# video.net
KiCad netlist of a schematic drawn in EAGLE
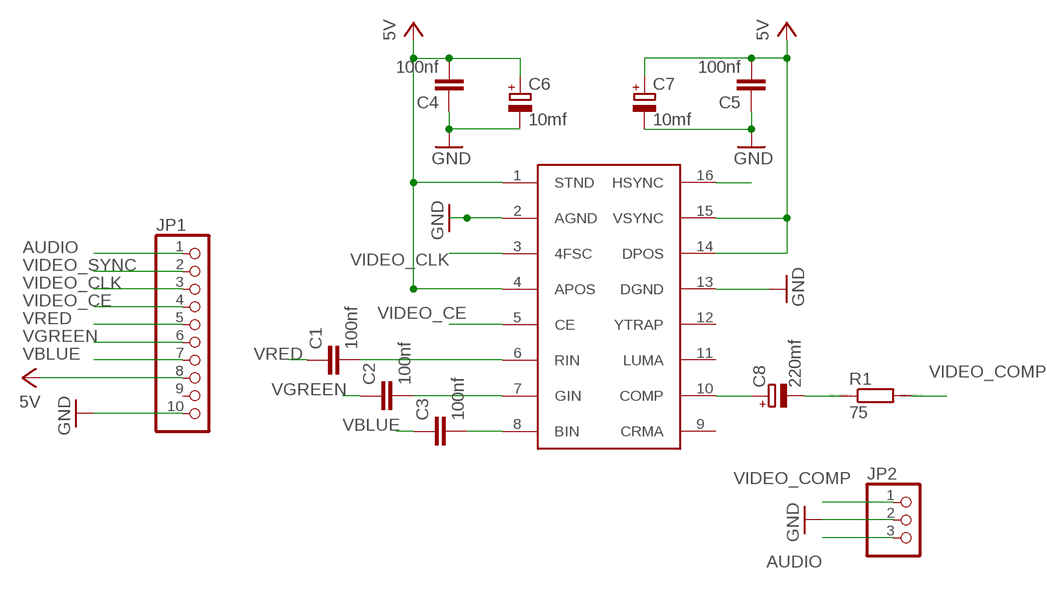
[diagram p0: schematic, sheet 1]

(export (version "E")
  (design (tool "Eeschema 10.0.6"))
  (components
    (comp (ref "C1")
      (value "100nf")
      (footprint "eagle-import:C0805")
      (libsource (lib "eagle-import") (part "C-EUC0805"))
    )
    (comp (ref "C2")
      (value "100nf")
      (footprint "eagle-import:C0805")
      (libsource (lib "eagle-import") (part "C-EUC0805"))
    )
    (comp (ref "C3")
      (value "100nf")
      (footprint "eagle-import:C0805")
      (libsource (lib "eagle-import") (part "C-EUC0805"))
    )
    (comp (ref "C4")
      (value "100nf")
      (footprint "eagle-import:C0805")
      (libsource (lib "eagle-import") (part "C-EUC0805"))
    )
    (comp (ref "C5")
      (value "100nf")
      (footprint "eagle-import:C0805")
      (libsource (lib "eagle-import") (part "C-EUC0805"))
    )
    (comp (ref "C6")
      (value "10mf")
      (footprint "eagle-import:E1,8-4")
      (libsource (lib "eagle-import") (part "CPOL-EUE1.8-4"))
    )
    (comp (ref "C7")
      (value "10mf")
      (footprint "eagle-import:E1,8-4")
      (libsource (lib "eagle-import") (part "CPOL-EUE1.8-4"))
    )
    (comp (ref "C8")
      (value "220mf")
      (footprint "eagle-import:E1,8-4")
      (libsource (lib "eagle-import") (part "CPOL-EUE1.8-4"))
    )
    (comp (ref "JP1")
      (value "PINHD-1X10")
      (footprint "eagle-import:1X10")
      (libsource (lib "eagle-import") (part "PINHD-1X10"))
    )
    (comp (ref "JP2")
      (value "PINHD-1X3")
      (footprint "eagle-import:1X03")
      (libsource (lib "eagle-import") (part "PINHD-1X3"))
    )
    (comp (ref "R1")
      (value "75")
      (footprint "eagle-import:R0805")
      (libsource (lib "eagle-import") (part "R-EU_R0805"))
    )
    (comp (ref "U$1")
      (value "AD725")
      (footprint "eagle-import:SO16W")
      (libsource (lib "eagle-import") (part "AD725"))
    )
  )
  (nets
    (net (code "1") (name "/AUDIO") (class "Default")
      (node (ref "JP1") (pin "1") (pinfunction "1_1") (pintype "passive"))
      (node (ref "JP2") (pin "3") (pinfunction "3_3") (pintype "passive"))
    )
    (net (code "2") (name "/VBLUE") (class "Default")
      (node (ref "C3") (pin "1") (pinfunction "1_1") (pintype "passive"))
      (node (ref "JP1") (pin "7") (pinfunction "7_7") (pintype "passive"))
    )
    (net (code "3") (name "/VGREEN") (class "Default")
      (node (ref "C2") (pin "1") (pinfunction "1_1") (pintype "passive"))
      (node (ref "JP1") (pin "6") (pinfunction "6_6") (pintype "passive"))
    )
    (net (code "4") (name "/VIDEO_CE") (class "Default")
      (node (ref "JP1") (pin "4") (pinfunction "4_4") (pintype "passive"))
      (node (ref "U$1") (pin "5") (pinfunction "CE_5") (pintype "bidirectional"))
    )
    (net (code "5") (name "/VIDEO_CLK") (class "Default")
      (node (ref "JP1") (pin "3") (pinfunction "3_3") (pintype "passive"))
      (node (ref "U$1") (pin "3") (pinfunction "4FSC_3") (pintype "bidirectional"))
    )
    (net (code "6") (name "/VIDEO_COMP") (class "Default")
      (node (ref "JP2") (pin "1") (pinfunction "1_1") (pintype "passive"))
      (node (ref "R1") (pin "2") (pinfunction "2_2") (pintype "passive"))
    )
    (net (code "7") (name "/VIDEO_SYNC") (class "Default")
      (node (ref "JP1") (pin "2") (pinfunction "2_2") (pintype "passive"))
      (node (ref "U$1") (pin "16") (pinfunction "HSYNC_16") (pintype "bidirectional"))
    )
    (net (code "8") (name "/VRED") (class "Default")
      (node (ref "C1") (pin "1") (pinfunction "1_1") (pintype "passive"))
      (node (ref "JP1") (pin "5") (pinfunction "5_5") (pintype "passive"))
    )
    (net (code "9") (name "5V") (class "Default")
      (node (ref "C4") (pin "2") (pinfunction "2_2") (pintype "passive"))
      (node (ref "C5") (pin "2") (pinfunction "2_2") (pintype "passive"))
      (node (ref "C6") (pin "+") (pinfunction "+_+") (pintype "passive"))
      (node (ref "C7") (pin "+") (pinfunction "+_+") (pintype "passive"))
      (node (ref "JP1") (pin "8") (pinfunction "8_8") (pintype "passive"))
      (node (ref "U$1") (pin "1") (pinfunction "STND_1") (pintype "bidirectional"))
      (node (ref "U$1") (pin "14") (pinfunction "DPOS_14") (pintype "bidirectional"))
      (node (ref "U$1") (pin "15") (pinfunction "VSYNC_15") (pintype "bidirectional"))
      (node (ref "U$1") (pin "4") (pinfunction "APOS_4") (pintype "bidirectional"))
    )
    (net (code "10") (name "GND") (class "Default")
      (node (ref "C4") (pin "1") (pinfunction "1_1") (pintype "passive"))
      (node (ref "C5") (pin "1") (pinfunction "1_1") (pintype "passive"))
      (node (ref "C6") (pin "-") (pinfunction "-_-") (pintype "passive"))
      (node (ref "C7") (pin "-") (pinfunction "-_-") (pintype "passive"))
      (node (ref "JP1") (pin "10") (pinfunction "10_10") (pintype "passive"))
      (node (ref "JP2") (pin "2") (pinfunction "2_2") (pintype "passive"))
      (node (ref "U$1") (pin "13") (pinfunction "DGND_13") (pintype "bidirectional"))
      (node (ref "U$1") (pin "2") (pinfunction "AGND_2") (pintype "bidirectional"))
    )
    (net (code "11") (name "Net-(C8-Pad-)") (class "Default")
      (node (ref "C8") (pin "-") (pinfunction "-_-") (pintype "passive"))
      (node (ref "R1") (pin "1") (pinfunction "1_1") (pintype "passive"))
    )
    (net (code "12") (name "Net-(U$1-BIN)") (class "Default")
      (node (ref "C3") (pin "2") (pinfunction "2_2") (pintype "passive"))
      (node (ref "U$1") (pin "8") (pinfunction "BIN_8") (pintype "bidirectional"))
    )
    (net (code "13") (name "Net-(U$1-COMP)") (class "Default")
      (node (ref "C8") (pin "+") (pinfunction "+_+") (pintype "passive"))
      (node (ref "U$1") (pin "10") (pinfunction "COMP_10") (pintype "bidirectional"))
    )
    (net (code "14") (name "Net-(U$1-GIN)") (class "Default")
      (node (ref "C2") (pin "2") (pinfunction "2_2") (pintype "passive"))
      (node (ref "U$1") (pin "7") (pinfunction "GIN_7") (pintype "bidirectional"))
    )
    (net (code "15") (name "Net-(U$1-RIN)") (class "Default")
      (node (ref "C1") (pin "2") (pinfunction "2_2") (pintype "passive"))
      (node (ref "U$1") (pin "6") (pinfunction "RIN_6") (pintype "bidirectional"))
    )
    (net (code "16") (name "unconnected-(JP1-Pad9)") (class "Default")
      (node (ref "JP1") (pin "9") (pinfunction "9_9") (pintype "passive"))
    )
    (net (code "17") (name "unconnected-(U$1-CRMA-Pad9)") (class "Default")
      (node (ref "U$1") (pin "9") (pinfunction "CRMA_9") (pintype "bidirectional"))
    )
    (net (code "18") (name "unconnected-(U$1-LUMA-Pad11)") (class "Default")
      (node (ref "U$1") (pin "11") (pinfunction "LUMA_11") (pintype "bidirectional"))
    )
    (net (code "19") (name "unconnected-(U$1-YTRAP-Pad12)") (class "Default")
      (node (ref "U$1") (pin "12") (pinfunction "YTRAP_12") (pintype "bidirectional"))
    )
  )
)
